# leer2.net
KiCad netlist of a schematic drawn in EAGLE
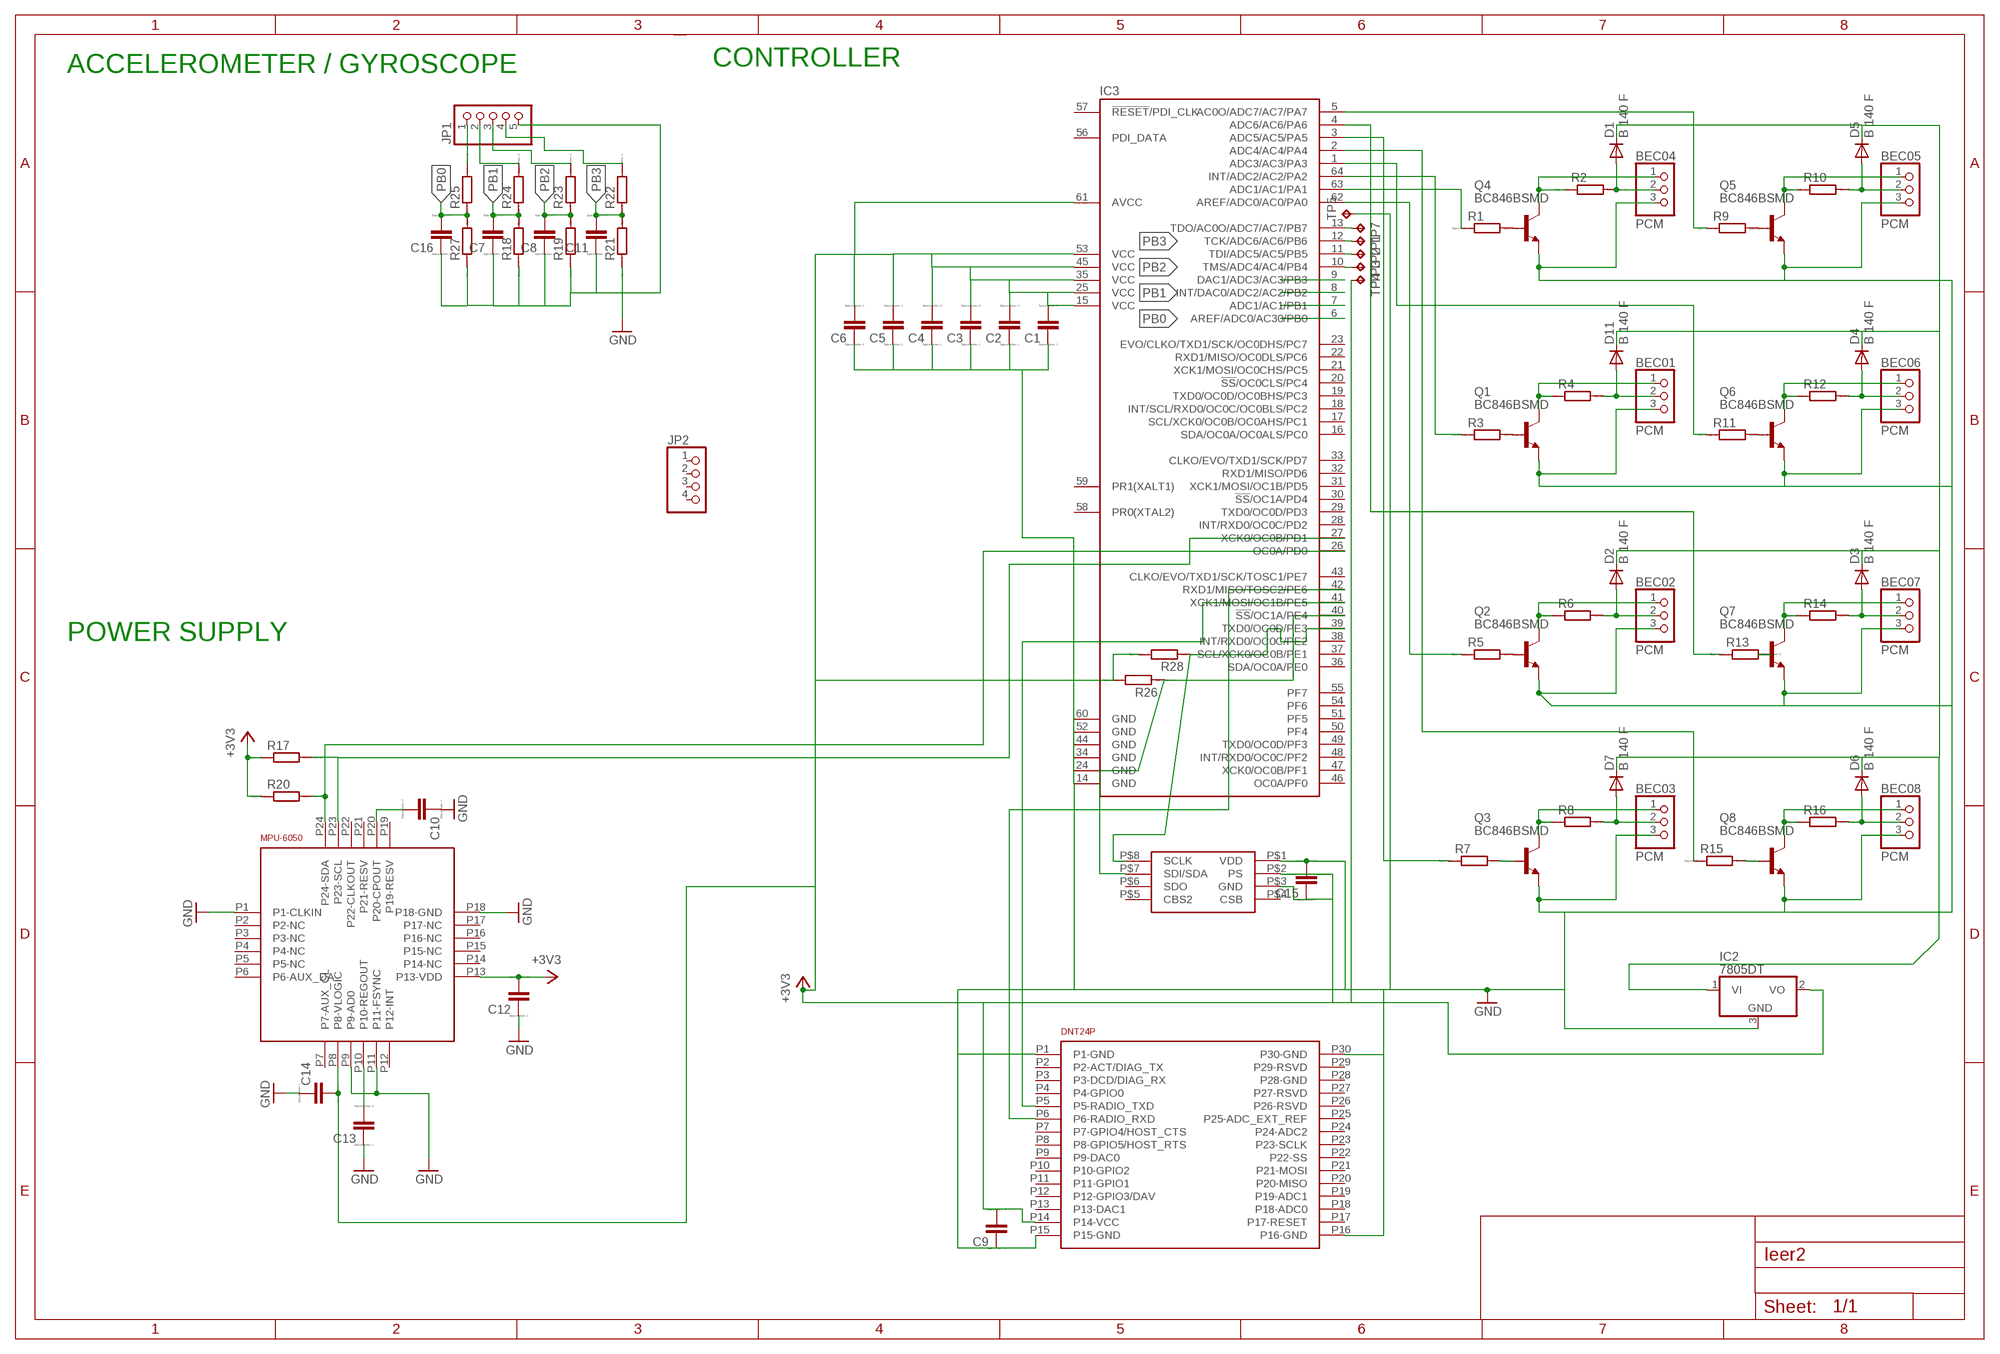
[diagram p0: schematic, sheet 1]

(export (version "E")
  (design (tool "Eeschema 10.0.6"))
  (components
    (comp (ref "BEC01")
      (value "PCM")
      (footprint "eagle-import:1X03")
      (libsource (lib "eagle-import") (part "PINHD-1X3"))
    )
    (comp (ref "BEC02")
      (value "PCM")
      (footprint "eagle-import:1X03")
      (libsource (lib "eagle-import") (part "PINHD-1X3"))
    )
    (comp (ref "BEC03")
      (value "PCM")
      (footprint "eagle-import:1X03")
      (libsource (lib "eagle-import") (part "PINHD-1X3"))
    )
    (comp (ref "BEC04")
      (value "PCM")
      (footprint "eagle-import:1X03")
      (libsource (lib "eagle-import") (part "PINHD-1X3"))
    )
    (comp (ref "BEC05")
      (value "PCM")
      (footprint "eagle-import:1X03")
      (libsource (lib "eagle-import") (part "PINHD-1X3"))
    )
    (comp (ref "BEC06")
      (value "PCM")
      (footprint "eagle-import:1X03")
      (libsource (lib "eagle-import") (part "PINHD-1X3"))
    )
    (comp (ref "BEC07")
      (value "PCM")
      (footprint "eagle-import:1X03")
      (libsource (lib "eagle-import") (part "PINHD-1X3"))
    )
    (comp (ref "BEC08")
      (value "PCM")
      (footprint "eagle-import:1X03")
      (libsource (lib "eagle-import") (part "PINHD-1X3"))
    )
    (comp (ref "C1")
      (value "CC0603")
      (footprint "eagle-import:C0603")
      (libsource (lib "eagle-import") (part "CC0603"))
    )
    (comp (ref "C2")
      (value "CC0603")
      (footprint "eagle-import:C0603")
      (libsource (lib "eagle-import") (part "CC0603"))
    )
    (comp (ref "C3")
      (value "CC0603")
      (footprint "eagle-import:C0603")
      (libsource (lib "eagle-import") (part "CC0603"))
    )
    (comp (ref "C4")
      (value "CC0603")
      (footprint "eagle-import:C0603")
      (libsource (lib "eagle-import") (part "CC0603"))
    )
    (comp (ref "C5")
      (value "CC0603")
      (footprint "eagle-import:C0603")
      (libsource (lib "eagle-import") (part "CC0603"))
    )
    (comp (ref "C6")
      (value "CC0603")
      (footprint "eagle-import:C0603")
      (libsource (lib "eagle-import") (part "CC0603"))
    )
    (comp (ref "C7")
      (value "CC0603")
      (footprint "eagle-import:C0603")
      (libsource (lib "eagle-import") (part "CC0603"))
    )
    (comp (ref "C8")
      (value "CC0603")
      (footprint "eagle-import:C0603")
      (libsource (lib "eagle-import") (part "CC0603"))
    )
    (comp (ref "C9")
      (value "CC0603")
      (footprint "eagle-import:C0603")
      (libsource (lib "eagle-import") (part "CC0603"))
    )
    (comp (ref "C10")
      (value "CC0603")
      (footprint "eagle-import:C0603")
      (libsource (lib "eagle-import") (part "CC0603"))
    )
    (comp (ref "C11")
      (value "CC0603")
      (footprint "eagle-import:C0603")
      (libsource (lib "eagle-import") (part "CC0603"))
    )
    (comp (ref "C12")
      (value "CC0603")
      (footprint "eagle-import:C0603")
      (libsource (lib "eagle-import") (part "CC0603"))
    )
    (comp (ref "C13")
      (value "CC0603")
      (footprint "eagle-import:C0603")
      (libsource (lib "eagle-import") (part "CC0603"))
    )
    (comp (ref "C14")
      (value "CC0603")
      (footprint "eagle-import:C0603")
      (libsource (lib "eagle-import") (part "CC0603"))
    )
    (comp (ref "C15")
      (value "CC0603")
      (footprint "eagle-import:C0603")
      (libsource (lib "eagle-import") (part "CC0603"))
    )
    (comp (ref "C16")
      (value "CC0603")
      (footprint "eagle-import:C0603")
      (libsource (lib "eagle-import") (part "CC0603"))
    )
    (comp (ref "D1")
      (value "B 140 F")
      (footprint "eagle-import:SOD-123_MINI-SMA")
      (libsource (lib "eagle-import") (part "CGRM400-G1"))
    )
    (comp (ref "D2")
      (value "B 140 F")
      (footprint "eagle-import:SOD-123_MINI-SMA")
      (libsource (lib "eagle-import") (part "CGRM400-G1"))
    )
    (comp (ref "D3")
      (value "B 140 F")
      (footprint "eagle-import:SOD-123_MINI-SMA")
      (libsource (lib "eagle-import") (part "CGRM400-G1"))
    )
    (comp (ref "D4")
      (value "B 140 F")
      (footprint "eagle-import:SOD-123_MINI-SMA")
      (libsource (lib "eagle-import") (part "CGRM400-G1"))
    )
    (comp (ref "D5")
      (value "B 140 F")
      (footprint "eagle-import:SOD-123_MINI-SMA")
      (libsource (lib "eagle-import") (part "CGRM400-G1"))
    )
    (comp (ref "D6")
      (value "B 140 F")
      (footprint "eagle-import:SOD-123_MINI-SMA")
      (libsource (lib "eagle-import") (part "CGRM400-G1"))
    )
    (comp (ref "D7")
      (value "B 140 F")
      (footprint "eagle-import:SOD-123_MINI-SMA")
      (libsource (lib "eagle-import") (part "CGRM400-G1"))
    )
    (comp (ref "D11")
      (value "B 140 F")
      (footprint "eagle-import:SOD-123_MINI-SMA")
      (libsource (lib "eagle-import") (part "CGRM400-G1"))
    )
    (comp (ref "IC2")
      (value "7805DT")
      (footprint "eagle-import:TO252")
      (libsource (lib "eagle-import") (part "78DT05"))
    )
    (comp (ref "IC3")
      (value "ATXMEGA##A3-64A")
      (footprint "eagle-import:TQFP-64")
      (libsource (lib "eagle-import") (part "ATXMEGA##A3-64A"))
    )
    (comp (ref "JP1")
      (value "PINHD-1X5/90")
      (footprint "eagle-import:1X05_90")
      (libsource (lib "eagle-import") (part "PINHD-1X5/90"))
    )
    (comp (ref "JP2")
      (value "PINHD-1X4/90")
      (footprint "eagle-import:1X04_90")
      (libsource (lib "eagle-import") (part "PINHD-1X4/90"))
    )
    (comp (ref "Q1")
      (value "BC846BSMD")
      (footprint "eagle-import:SOT23")
      (libsource (lib "eagle-import") (part "BC846SMDB"))
    )
    (comp (ref "Q2")
      (value "BC846BSMD")
      (footprint "eagle-import:SOT23")
      (libsource (lib "eagle-import") (part "BC846SMDB"))
    )
    (comp (ref "Q3")
      (value "BC846BSMD")
      (footprint "eagle-import:SOT23")
      (libsource (lib "eagle-import") (part "BC846SMDB"))
    )
    (comp (ref "Q4")
      (value "BC846BSMD")
      (footprint "eagle-import:SOT23")
      (libsource (lib "eagle-import") (part "BC846SMDB"))
    )
    (comp (ref "Q5")
      (value "BC846BSMD")
      (footprint "eagle-import:SOT23")
      (libsource (lib "eagle-import") (part "BC846SMDB"))
    )
    (comp (ref "Q6")
      (value "BC846BSMD")
      (footprint "eagle-import:SOT23")
      (libsource (lib "eagle-import") (part "BC846SMDB"))
    )
    (comp (ref "Q7")
      (value "BC846BSMD")
      (footprint "eagle-import:SOT23")
      (libsource (lib "eagle-import") (part "BC846SMDB"))
    )
    (comp (ref "Q8")
      (value "BC846BSMD")
      (footprint "eagle-import:SOT23")
      (libsource (lib "eagle-import") (part "BC846SMDB"))
    )
    (comp (ref "R1")
      (value "RR0603")
      (footprint "eagle-import:R0603")
      (libsource (lib "eagle-import") (part "RR0603"))
    )
    (comp (ref "R2")
      (value "RR0603")
      (footprint "eagle-import:R0603")
      (libsource (lib "eagle-import") (part "RR0603"))
    )
    (comp (ref "R3")
      (value "RR0603")
      (footprint "eagle-import:R0603")
      (libsource (lib "eagle-import") (part "RR0603"))
    )
    (comp (ref "R4")
      (value "RR0603")
      (footprint "eagle-import:R0603")
      (libsource (lib "eagle-import") (part "RR0603"))
    )
    (comp (ref "R5")
      (value "RR0603")
      (footprint "eagle-import:R0603")
      (libsource (lib "eagle-import") (part "RR0603"))
    )
    (comp (ref "R6")
      (value "RR0603")
      (footprint "eagle-import:R0603")
      (libsource (lib "eagle-import") (part "RR0603"))
    )
    (comp (ref "R7")
      (value "RR0603")
      (footprint "eagle-import:R0603")
      (libsource (lib "eagle-import") (part "RR0603"))
    )
    (comp (ref "R8")
      (value "RR0603")
      (footprint "eagle-import:R0603")
      (libsource (lib "eagle-import") (part "RR0603"))
    )
    (comp (ref "R9")
      (value "RR0603")
      (footprint "eagle-import:R0603")
      (libsource (lib "eagle-import") (part "RR0603"))
    )
    (comp (ref "R10")
      (value "RR0603")
      (footprint "eagle-import:R0603")
      (libsource (lib "eagle-import") (part "RR0603"))
    )
    (comp (ref "R11")
      (value "RR0603")
      (footprint "eagle-import:R0603")
      (libsource (lib "eagle-import") (part "RR0603"))
    )
    (comp (ref "R12")
      (value "RR0603")
      (footprint "eagle-import:R0603")
      (libsource (lib "eagle-import") (part "RR0603"))
    )
    (comp (ref "R13")
      (value "RR0603")
      (footprint "eagle-import:R0603")
      (libsource (lib "eagle-import") (part "RR0603"))
    )
    (comp (ref "R14")
      (value "RR0603")
      (footprint "eagle-import:R0603")
      (libsource (lib "eagle-import") (part "RR0603"))
    )
    (comp (ref "R15")
      (value "RR0603")
      (footprint "eagle-import:R0603")
      (libsource (lib "eagle-import") (part "RR0603"))
    )
    (comp (ref "R16")
      (value "RR0603")
      (footprint "eagle-import:R0603")
      (libsource (lib "eagle-import") (part "RR0603"))
    )
    (comp (ref "R17")
      (value "RR0603")
      (footprint "eagle-import:R0603")
      (libsource (lib "eagle-import") (part "RR0603"))
    )
    (comp (ref "R18")
      (value "RR0603")
      (footprint "eagle-import:R0603")
      (libsource (lib "eagle-import") (part "RR0603"))
    )
    (comp (ref "R19")
      (value "RR0603")
      (footprint "eagle-import:R0603")
      (libsource (lib "eagle-import") (part "RR0603"))
    )
    (comp (ref "R20")
      (value "RR0603")
      (footprint "eagle-import:R0603")
      (libsource (lib "eagle-import") (part "RR0603"))
    )
    (comp (ref "R21")
      (value "RR0603")
      (footprint "eagle-import:R0603")
      (libsource (lib "eagle-import") (part "RR0603"))
    )
    (comp (ref "R22")
      (value "RR0603")
      (footprint "eagle-import:R0603")
      (libsource (lib "eagle-import") (part "RR0603"))
    )
    (comp (ref "R23")
      (value "RR0603")
      (footprint "eagle-import:R0603")
      (libsource (lib "eagle-import") (part "RR0603"))
    )
    (comp (ref "R24")
      (value "RR0603")
      (footprint "eagle-import:R0603")
      (libsource (lib "eagle-import") (part "RR0603"))
    )
    (comp (ref "R25")
      (value "RR0603")
      (footprint "eagle-import:R0603")
      (libsource (lib "eagle-import") (part "RR0603"))
    )
    (comp (ref "R26")
      (value "RR0603")
      (footprint "eagle-import:R0603")
      (libsource (lib "eagle-import") (part "RR0603"))
    )
    (comp (ref "R27")
      (value "RR0603")
      (footprint "eagle-import:R0603")
      (libsource (lib "eagle-import") (part "RR0603"))
    )
    (comp (ref "R28")
      (value "RR0603")
      (footprint "eagle-import:R0603")
      (libsource (lib "eagle-import") (part "RR0603"))
    )
    (comp (ref "TP1")
      (value "TPTP08R")
      (footprint "eagle-import:TP08R")
      (libsource (lib "eagle-import") (part "TPTP08R"))
    )
    (comp (ref "TP2")
      (value "TPTP08R")
      (footprint "eagle-import:TP08R")
      (libsource (lib "eagle-import") (part "TPTP08R"))
    )
    (comp (ref "TP3")
      (value "TPTP08R")
      (footprint "eagle-import:TP08R")
      (libsource (lib "eagle-import") (part "TPTP08R"))
    )
    (comp (ref "TP4")
      (value "TPTP08R")
      (footprint "eagle-import:TP08R")
      (libsource (lib "eagle-import") (part "TPTP08R"))
    )
    (comp (ref "TP5")
      (value "TPTP08R")
      (footprint "eagle-import:TP08R")
      (libsource (lib "eagle-import") (part "TPTP08R"))
    )
    (comp (ref "TP7")
      (value "TPTP08R")
      (footprint "eagle-import:TP08R")
      (libsource (lib "eagle-import") (part "TPTP08R"))
    )
    (comp (ref "U$1")
      (value "DNT24P_RADIO_MODULE")
      (footprint "eagle-import:DNT24P_RADIO_MODULE")
      (libsource (lib "eagle-import") (part "DNT24P_RADIO_MODULE"))
    )
    (comp (ref "U$2")
      (value "MS5611")
      (footprint "eagle-import:01BA03")
      (libsource (lib "eagle-import") (part "MS5611"))
    )
    (comp (ref "U$3")
      (value "MPU-6050_ACC_GYRO")
      (footprint "eagle-import:MPU-6050_ACC_GYRO")
      (libsource (lib "eagle-import") (part "MPU-6050_ACC_GYRO"))
    )
  )
  (nets
    (net (code "1") (name "+3V3") (class "Default")
      (node (ref "C1") (pin "2") (pinfunction "2_2") (pintype "passive"))
      (node (ref "C12") (pin "2") (pinfunction "2_2") (pintype "passive"))
      (node (ref "C14") (pin "2") (pinfunction "2_2") (pintype "passive"))
      (node (ref "C15") (pin "1") (pinfunction "1_1") (pintype "passive"))
      (node (ref "C2") (pin "2") (pinfunction "2_2") (pintype "passive"))
      (node (ref "C3") (pin "2") (pinfunction "2_2") (pintype "passive"))
      (node (ref "C4") (pin "2") (pinfunction "2_2") (pintype "passive"))
      (node (ref "C5") (pin "2") (pinfunction "2_2") (pintype "passive"))
      (node (ref "C6") (pin "2") (pinfunction "2_2") (pintype "passive"))
      (node (ref "C9") (pin "2") (pinfunction "2_2") (pintype "passive"))
      (node (ref "IC2") (pin "2") (pinfunction "VO_2") (pintype "passive"))
      (node (ref "IC3") (pin "15") (pinfunction "VCC_15") (pintype "power_in"))
      (node (ref "IC3") (pin "25") (pinfunction "VCC_25") (pintype "power_in"))
      (node (ref "IC3") (pin "35") (pinfunction "VCC_35") (pintype "power_in"))
      (node (ref "IC3") (pin "45") (pinfunction "VCC_45") (pintype "power_in"))
      (node (ref "IC3") (pin "53") (pinfunction "VCC_53") (pintype "power_in"))
      (node (ref "IC3") (pin "61") (pinfunction "AVCC_61") (pintype "power_in"))
      (node (ref "R17") (pin "1") (pinfunction "1_1") (pintype "passive"))
      (node (ref "R20") (pin "1") (pinfunction "1_1") (pintype "passive"))
      (node (ref "R26") (pin "2") (pinfunction "2_2") (pintype "passive"))
      (node (ref "R28") (pin "2") (pinfunction "2_2") (pintype "passive"))
      (node (ref "TP4") (pin "TP") (pinfunction "TP_TP") (pintype "input"))
      (node (ref "U$1") (pin "P14") (pinfunction "P14-VCC_P14") (pintype "bidirectional"))
      (node (ref "U$2") (pin "P$2") (pinfunction "PS_P$2") (pintype "bidirectional"))
      (node (ref "U$2") (pin "P$3") (pinfunction "GND_P$3") (pintype "bidirectional"))
      (node (ref "U$3") (pin "P13") (pinfunction "P13-VDD_P13") (pintype "bidirectional"))
      (node (ref "U$3") (pin "P8") (pinfunction "P8-VLOGIC_P8") (pintype "bidirectional"))
    )
    (net (code "2") (name "GND") (class "Default")
      (node (ref "BEC01") (pin "3") (pinfunction "3_3") (pintype "passive"))
      (node (ref "BEC02") (pin "3") (pinfunction "3_3") (pintype "passive"))
      (node (ref "BEC03") (pin "3") (pinfunction "3_3") (pintype "passive"))
      (node (ref "BEC04") (pin "3") (pinfunction "3_3") (pintype "passive"))
      (node (ref "BEC05") (pin "3") (pinfunction "3_3") (pintype "passive"))
      (node (ref "BEC06") (pin "3") (pinfunction "3_3") (pintype "passive"))
      (node (ref "BEC07") (pin "3") (pinfunction "3_3") (pintype "passive"))
      (node (ref "BEC08") (pin "3") (pinfunction "3_3") (pintype "passive"))
      (node (ref "C1") (pin "1") (pinfunction "1_1") (pintype "passive"))
      (node (ref "C10") (pin "1") (pinfunction "1_1") (pintype "passive"))
      (node (ref "C11") (pin "1") (pinfunction "1_1") (pintype "passive"))
      (node (ref "C12") (pin "1") (pinfunction "1_1") (pintype "passive"))
      (node (ref "C13") (pin "1") (pinfunction "1_1") (pintype "passive"))
      (node (ref "C14") (pin "1") (pinfunction "1_1") (pintype "passive"))
      (node (ref "C15") (pin "2") (pinfunction "2_2") (pintype "passive"))
      (node (ref "C16") (pin "1") (pinfunction "1_1") (pintype "passive"))
      (node (ref "C2") (pin "1") (pinfunction "1_1") (pintype "passive"))
      (node (ref "C3") (pin "1") (pinfunction "1_1") (pintype "passive"))
      (node (ref "C4") (pin "1") (pinfunction "1_1") (pintype "passive"))
      (node (ref "C5") (pin "1") (pinfunction "1_1") (pintype "passive"))
      (node (ref "C6") (pin "1") (pinfunction "1_1") (pintype "passive"))
      (node (ref "C7") (pin "1") (pinfunction "1_1") (pintype "passive"))
      (node (ref "C8") (pin "1") (pinfunction "1_1") (pintype "passive"))
      (node (ref "C9") (pin "1") (pinfunction "1_1") (pintype "passive"))
      (node (ref "IC2") (pin "3") (pinfunction "GND_3") (pintype "passive"))
      (node (ref "IC3") (pin "14") (pinfunction "GND_14") (pintype "power_in"))
      (node (ref "IC3") (pin "24") (pinfunction "GND_24") (pintype "power_in"))
      (node (ref "IC3") (pin "34") (pinfunction "GND_34") (pintype "power_in"))
      (node (ref "IC3") (pin "44") (pinfunction "GND_44") (pintype "power_in"))
      (node (ref "IC3") (pin "52") (pinfunction "GND_52") (pintype "power_in"))
      (node (ref "IC3") (pin "60") (pinfunction "GND_60") (pintype "power_in"))
      (node (ref "JP1") (pin "5") (pinfunction "5_5") (pintype "passive"))
      (node (ref "Q1") (pin "2") (pinfunction "E_2") (pintype "passive"))
      (node (ref "Q2") (pin "2") (pinfunction "E_2") (pintype "passive"))
      (node (ref "Q3") (pin "2") (pinfunction "E_2") (pintype "passive"))
      (node (ref "Q4") (pin "2") (pinfunction "E_2") (pintype "passive"))
      (node (ref "Q5") (pin "2") (pinfunction "E_2") (pintype "passive"))
      (node (ref "Q6") (pin "2") (pinfunction "E_2") (pintype "passive"))
      (node (ref "Q7") (pin "2") (pinfunction "E_2") (pintype "passive"))
      (node (ref "Q8") (pin "2") (pinfunction "E_2") (pintype "passive"))
      (node (ref "R18") (pin "1") (pinfunction "1_1") (pintype "passive"))
      (node (ref "R19") (pin "1") (pinfunction "1_1") (pintype "passive"))
      (node (ref "R21") (pin "1") (pinfunction "1_1") (pintype "passive"))
      (node (ref "R27") (pin "1") (pinfunction "1_1") (pintype "passive"))
      (node (ref "TP5") (pin "TP") (pinfunction "TP_TP") (pintype "input"))
      (node (ref "U$1") (pin "P1") (pinfunction "P1-GND_P1") (pintype "bidirectional"))
      (node (ref "U$1") (pin "P15") (pinfunction "P15-GND_P15") (pintype "bidirectional"))
      (node (ref "U$1") (pin "P16") (pinfunction "P16-GND_P16") (pintype "bidirectional"))
      (node (ref "U$1") (pin "P30") (pinfunction "P30-GND_P30") (pintype "bidirectional"))
      (node (ref "U$2") (pin "P$1") (pinfunction "VDD_P$1") (pintype "bidirectional"))
      (node (ref "U$3") (pin "P1") (pinfunction "P1-CLKIN_P1") (pintype "bidirectional"))
      (node (ref "U$3") (pin "P11") (pinfunction "P11-FSYNC_P11") (pintype "bidirectional"))
      (node (ref "U$3") (pin "P18") (pinfunction "P18-GND_P18") (pintype "bidirectional"))
      (node (ref "U$3") (pin "P9") (pinfunction "P9-AD0_P9") (pintype "bidirectional"))
    )
    (net (code "3") (name "Net-(BEC01-Pad2)") (class "Default")
      (node (ref "BEC01") (pin "2") (pinfunction "2_2") (pintype "passive"))
      (node (ref "D11") (pin "A") (pinfunction "A_A") (pintype "passive"))
      (node (ref "R4") (pin "2") (pinfunction "2_2") (pintype "passive"))
    )
    (net (code "4") (name "Net-(BEC02-Pad2)") (class "Default")
      (node (ref "BEC02") (pin "2") (pinfunction "2_2") (pintype "passive"))
      (node (ref "D2") (pin "A") (pinfunction "A_A") (pintype "passive"))
      (node (ref "R6") (pin "2") (pinfunction "2_2") (pintype "passive"))
    )
    (net (code "5") (name "Net-(BEC03-Pad2)") (class "Default")
      (node (ref "BEC03") (pin "2") (pinfunction "2_2") (pintype "passive"))
      (node (ref "D7") (pin "A") (pinfunction "A_A") (pintype "passive"))
      (node (ref "R8") (pin "2") (pinfunction "2_2") (pintype "passive"))
    )
    (net (code "6") (name "Net-(BEC04-Pad2)") (class "Default")
      (node (ref "BEC04") (pin "2") (pinfunction "2_2") (pintype "passive"))
      (node (ref "D1") (pin "A") (pinfunction "A_A") (pintype "passive"))
      (node (ref "R2") (pin "2") (pinfunction "2_2") (pintype "passive"))
    )
    (net (code "7") (name "Net-(BEC05-Pad2)") (class "Default")
      (node (ref "BEC05") (pin "2") (pinfunction "2_2") (pintype "passive"))
      (node (ref "D5") (pin "A") (pinfunction "A_A") (pintype "passive"))
      (node (ref "R10") (pin "2") (pinfunction "2_2") (pintype "passive"))
    )
    (net (code "8") (name "Net-(BEC06-Pad2)") (class "Default")
      (node (ref "BEC06") (pin "2") (pinfunction "2_2") (pintype "passive"))
      (node (ref "D4") (pin "A") (pinfunction "A_A") (pintype "passive"))
      (node (ref "R12") (pin "2") (pinfunction "2_2") (pintype "passive"))
    )
    (net (code "9") (name "Net-(BEC07-Pad2)") (class "Default")
      (node (ref "BEC07") (pin "2") (pinfunction "2_2") (pintype "passive"))
      (node (ref "D3") (pin "A") (pinfunction "A_A") (pintype "passive"))
      (node (ref "R14") (pin "2") (pinfunction "2_2") (pintype "passive"))
    )
    (net (code "10") (name "Net-(BEC08-Pad2)") (class "Default")
      (node (ref "BEC08") (pin "2") (pinfunction "2_2") (pintype "passive"))
      (node (ref "D6") (pin "A") (pinfunction "A_A") (pintype "passive"))
      (node (ref "R16") (pin "2") (pinfunction "2_2") (pintype "passive"))
    )
    (net (code "11") (name "Net-(IC2-VI)") (class "Default")
      (node (ref "D1") (pin "C") (pinfunction "C_C") (pintype "passive"))
      (node (ref "D11") (pin "C") (pinfunction "C_C") (pintype "passive"))
      (node (ref "D2") (pin "C") (pinfunction "C_C") (pintype "passive"))
      (node (ref "D3") (pin "C") (pinfunction "C_C") (pintype "passive"))
      (node (ref "D4") (pin "C") (pinfunction "C_C") (pintype "passive"))
      (node (ref "D5") (pin "C") (pinfunction "C_C") (pintype "passive"))
      (node (ref "D6") (pin "C") (pinfunction "C_C") (pintype "passive"))
      (node (ref "D7") (pin "C") (pinfunction "C_C") (pintype "passive"))
      (node (ref "IC2") (pin "1") (pinfunction "VI_1") (pintype "input"))
    )
    (net (code "12") (name "Net-(IC3-AC0O{slash}ADC7{slash}AC7{slash}PA7)") (class "Default")
      (node (ref "IC3") (pin "5") (pinfunction "AC0O/ADC7/AC7/PA7_5") (pintype "bidirectional"))
      (node (ref "R9") (pin "1") (pinfunction "1_1") (pintype "passive"))
    )
    (net (code "13") (name "Net-(IC3-ADC1{slash}AC1{slash}PA1)") (class "Default")
      (node (ref "IC3") (pin "63") (pinfunction "ADC1/AC1/PA1_63") (pintype "bidirectional"))
      (node (ref "R1") (pin "1") (pinfunction "1_1") (pintype "passive"))
    )
    (net (code "14") (name "Net-(IC3-ADC3{slash}AC3{slash}PA3)") (class "Default")
      (node (ref "IC3") (pin "1") (pinfunction "ADC3/AC3/PA3_1") (pintype "bidirectional"))
      (node (ref "R11") (pin "1") (pinfunction "1_1") (pintype "passive"))
    )
    (net (code "15") (name "Net-(IC3-ADC4{slash}AC4{slash}PA4)") (class "Default")
      (node (ref "IC3") (pin "2") (pinfunction "ADC4/AC4/PA4_2") (pintype "bidirectional"))
      (node (ref "R15") (pin "1") (pinfunction "1_1") (pintype "passive"))
    )
    (net (code "16") (name "Net-(IC3-ADC5{slash}AC5{slash}PA5)") (class "Default")
      (node (ref "IC3") (pin "3") (pinfunction "ADC5/AC5/PA5_3") (pintype "bidirectional"))
      (node (ref "R7") (pin "1") (pinfunction "1_1") (pintype "passive"))
    )
    (net (code "17") (name "Net-(IC3-ADC6{slash}AC6{slash}PA6)") (class "Default")
      (node (ref "IC3") (pin "4") (pinfunction "ADC6/AC6/PA6_4") (pintype "bidirectional"))
      (node (ref "R13") (pin "1") (pinfunction "1_1") (pintype "passive"))
    )
    (net (code "18") (name "Net-(IC3-AREF{slash}ADC0{slash}AC0{slash}PA0)") (class "Default")
      (node (ref "IC3") (pin "62") (pinfunction "AREF/ADC0/AC0/PA0_62") (pintype "bidirectional"))
      (node (ref "R5") (pin "1") (pinfunction "1_1") (pintype "passive"))
    )
    (net (code "19") (name "Net-(IC3-INT{slash}ADC2{slash}AC2{slash}PA2)") (class "Default")
      (node (ref "IC3") (pin "64") (pinfunction "INT/ADC2/AC2/PA2_64") (pintype "bidirectional"))
      (node (ref "R3") (pin "1") (pinfunction "1_1") (pintype "passive"))
    )
    (net (code "20") (name "Net-(IC3-OC0A{slash}PD0)") (class "Default")
      (node (ref "IC3") (pin "26") (pinfunction "OC0A/PD0_26") (pintype "bidirectional"))
      (node (ref "R20") (pin "2") (pinfunction "2_2") (pintype "passive"))
      (node (ref "U$3") (pin "P24") (pinfunction "P24-SDA_P24") (pintype "bidirectional"))
    )
    (net (code "21") (name "Net-(IC3-RXD1{slash}MISO{slash}TOSC2{slash}PE6)") (class "Default")
      (node (ref "IC3") (pin "42") (pinfunction "RXD1/MISO/TOSC2/PE6_42") (pintype "bidirectional"))
      (node (ref "U$1") (pin "P6") (pinfunction "P6-RADIO_RXD_P6") (pintype "bidirectional"))
    )
    (net (code "22") (name "Net-(IC3-TCK{slash}ADC6{slash}AC6{slash}PB6)") (class "Default")
      (node (ref "IC3") (pin "12") (pinfunction "TCK/ADC6/AC6/PB6_12") (pintype "bidirectional"))
      (node (ref "TP1") (pin "TP") (pinfunction "TP_TP") (pintype "input"))
    )
    (net (code "23") (name "Net-(IC3-TDI{slash}ADC5{slash}AC5{slash}PB5)") (class "Default")
      (node (ref "IC3") (pin "11") (pinfunction "TDI/ADC5/AC5/PB5_11") (pintype "bidirectional"))
      (node (ref "TP2") (pin "TP") (pinfunction "TP_TP") (pintype "input"))
    )
    (net (code "24") (name "Net-(IC3-TDO{slash}AC0O{slash}ADC7{slash}AC7{slash}PB7)") (class "Default")
      (node (ref "IC3") (pin "13") (pinfunction "TDO/AC0O/ADC7/AC7/PB7_13") (pintype "bidirectional"))
      (node (ref "TP7") (pin "TP") (pinfunction "TP_TP") (pintype "input"))
    )
    (net (code "25") (name "Net-(IC3-TMS{slash}ADC4{slash}AC4{slash}PB4)") (class "Default")
      (node (ref "IC3") (pin "10") (pinfunction "TMS/ADC4/AC4/PB4_10") (pintype "bidirectional"))
      (node (ref "TP3") (pin "TP") (pinfunction "TP_TP") (pintype "input"))
    )
    (net (code "26") (name "Net-(IC3-TXD0{slash}OC0D{slash}PE3)") (class "Default")
      (node (ref "IC3") (pin "39") (pinfunction "TXD0/OC0D/PE3_39") (pintype "bidirectional"))
      (node (ref "R28") (pin "1") (pinfunction "1_1") (pintype "passive"))
      (node (ref "U$2") (pin "P$8") (pinfunction "SCLK_P$8") (pintype "bidirectional"))
    )
    (net (code "27") (name "Net-(IC3-XCK0{slash}OC0B{slash}PD1)") (class "Default")
      (node (ref "IC3") (pin "27") (pinfunction "XCK0/OC0B/PD1_27") (pintype "bidirectional"))
      (node (ref "R17") (pin "2") (pinfunction "2_2") (pintype "passive"))
      (node (ref "U$3") (pin "P23") (pinfunction "P23-SCL_P23") (pintype "bidirectional"))
    )
    (net (code "28") (name "Net-(IC3-XCK1{slash}MOSI{slash}OC1B{slash}PE5)") (class "Default")
      (node (ref "IC3") (pin "41") (pinfunction "XCK1/MOSI/OC1B/PE5_41") (pintype "bidirectional"))
      (node (ref "U$1") (pin "P5") (pinfunction "P5-RADIO_TXD_P5") (pintype "bidirectional"))
    )
    (net (code "29") (name "Net-(IC3-~{SS}{slash}OC1A{slash}PE4)") (class "Default")
      (node (ref "IC3") (pin "40") (pinfunction "~{SS}/OC1A/PE4_40") (pintype "bidirectional"))
      (node (ref "R26") (pin "1") (pinfunction "1_1") (pintype "passive"))
      (node (ref "U$2") (pin "P$7") (pinfunction "SDI/SDA_P$7") (pintype "bidirectional"))
    )
    (net (code "30") (name "Net-(JP1-Pad1)") (class "Default")
      (node (ref "JP1") (pin "1") (pinfunction "1_1") (pintype "passive"))
      (node (ref "R25") (pin "2") (pinfunction "2_2") (pintype "passive"))
    )
    (net (code "31") (name "Net-(JP1-Pad2)") (class "Default")
      (node (ref "JP1") (pin "2") (pinfunction "2_2") (pintype "passive"))
      (node (ref "R24") (pin "2") (pinfunction "2_2") (pintype "passive"))
    )
    (net (code "32") (name "Net-(JP1-Pad3)") (class "Default")
      (node (ref "JP1") (pin "3") (pinfunction "3_3") (pintype "passive"))
      (node (ref "R23") (pin "2") (pinfunction "2_2") (pintype "passive"))
    )
    (net (code "33") (name "Net-(JP1-Pad4)") (class "Default")
      (node (ref "JP1") (pin "4") (pinfunction "4_4") (pintype "passive"))
      (node (ref "R22") (pin "2") (pinfunction "2_2") (pintype "passive"))
    )
    (net (code "34") (name "Net-(Q1-B)") (class "Default")
      (node (ref "Q1") (pin "1") (pinfunction "B_1") (pintype "passive"))
      (node (ref "R3") (pin "2") (pinfunction "2_2") (pintype "passive"))
    )
    (net (code "35") (name "Net-(Q1-C)") (class "Default")
      (node (ref "BEC01") (pin "1") (pinfunction "1_1") (pintype "passive"))
      (node (ref "Q1") (pin "3") (pinfunction "C_3") (pintype "passive"))
      (node (ref "R4") (pin "1") (pinfunction "1_1") (pintype "passive"))
    )
    (net (code "36") (name "Net-(Q2-B)") (class "Default")
      (node (ref "Q2") (pin "1") (pinfunction "B_1") (pintype "passive"))
      (node (ref "R5") (pin "2") (pinfunction "2_2") (pintype "passive"))
    )
    (net (code "37") (name "Net-(Q2-C)") (class "Default")
      (node (ref "BEC02") (pin "1") (pinfunction "1_1") (pintype "passive"))
      (node (ref "Q2") (pin "3") (pinfunction "C_3") (pintype "passive"))
      (node (ref "R6") (pin "1") (pinfunction "1_1") (pintype "passive"))
    )
    (net (code "38") (name "Net-(Q3-B)") (class "Default")
      (node (ref "Q3") (pin "1") (pinfunction "B_1") (pintype "passive"))
      (node (ref "R7") (pin "2") (pinfunction "2_2") (pintype "passive"))
    )
    (net (code "39") (name "Net-(Q3-C)") (class "Default")
      (node (ref "BEC03") (pin "1") (pinfunction "1_1") (pintype "passive"))
      (node (ref "Q3") (pin "3") (pinfunction "C_3") (pintype "passive"))
      (node (ref "R8") (pin "1") (pinfunction "1_1") (pintype "passive"))
    )
    (net (code "40") (name "Net-(Q4-B)") (class "Default")
      (node (ref "Q4") (pin "1") (pinfunction "B_1") (pintype "passive"))
      (node (ref "R1") (pin "2") (pinfunction "2_2") (pintype "passive"))
    )
    (net (code "41") (name "Net-(Q4-C)") (class "Default")
      (node (ref "BEC04") (pin "1") (pinfunction "1_1") (pintype "passive"))
      (node (ref "Q4") (pin "3") (pinfunction "C_3") (pintype "passive"))
      (node (ref "R2") (pin "1") (pinfunction "1_1") (pintype "passive"))
    )
    (net (code "42") (name "Net-(Q5-B)") (class "Default")
      (node (ref "Q5") (pin "1") (pinfunction "B_1") (pintype "passive"))
      (node (ref "R9") (pin "2") (pinfunction "2_2") (pintype "passive"))
    )
    (net (code "43") (name "Net-(Q5-C)") (class "Default")
      (node (ref "BEC05") (pin "1") (pinfunction "1_1") (pintype "passive"))
      (node (ref "Q5") (pin "3") (pinfunction "C_3") (pintype "passive"))
      (node (ref "R10") (pin "1") (pinfunction "1_1") (pintype "passive"))
    )
    (net (code "44") (name "Net-(Q6-B)") (class "Default")
      (node (ref "Q6") (pin "1") (pinfunction "B_1") (pintype "passive"))
      (node (ref "R11") (pin "2") (pinfunction "2_2") (pintype "passive"))
    )
    (net (code "45") (name "Net-(Q6-C)") (class "Default")
      (node (ref "BEC06") (pin "1") (pinfunction "1_1") (pintype "passive"))
      (node (ref "Q6") (pin "3") (pinfunction "C_3") (pintype "passive"))
      (node (ref "R12") (pin "1") (pinfunction "1_1") (pintype "passive"))
    )
    (net (code "46") (name "Net-(Q7-B)") (class "Default")
      (node (ref "Q7") (pin "1") (pinfunction "B_1") (pintype "passive"))
      (node (ref "R13") (pin "2") (pinfunction "2_2") (pintype "passive"))
    )
    (net (code "47") (name "Net-(Q7-C)") (class "Default")
      (node (ref "BEC07") (pin "1") (pinfunction "1_1") (pintype "passive"))
      (node (ref "Q7") (pin "3") (pinfunction "C_3") (pintype "passive"))
      (node (ref "R14") (pin "1") (pinfunction "1_1") (pintype "passive"))
    )
    (net (code "48") (name "Net-(Q8-B)") (class "Default")
      (node (ref "Q8") (pin "1") (pinfunction "B_1") (pintype "passive"))
      (node (ref "R15") (pin "2") (pinfunction "2_2") (pintype "passive"))
    )
    (net (code "49") (name "Net-(Q8-C)") (class "Default")
      (node (ref "BEC08") (pin "1") (pinfunction "1_1") (pintype "passive"))
      (node (ref "Q8") (pin "3") (pinfunction "C_3") (pintype "passive"))
      (node (ref "R16") (pin "1") (pinfunction "1_1") (pintype "passive"))
    )
    (net (code "50") (name "Net-(U$3-P10-REGOUT)") (class "Default")
      (node (ref "C13") (pin "2") (pinfunction "2_2") (pintype "passive"))
      (node (ref "U$3") (pin "P10") (pinfunction "P10-REGOUT_P10") (pintype "bidirectional"))
    )
    (net (code "51") (name "Net-(U$3-P20-CPOUT)") (class "Default")
      (node (ref "C10") (pin "2") (pinfunction "2_2") (pintype "passive"))
      (node (ref "U$3") (pin "P20") (pinfunction "P20-CPOUT_P20") (pintype "bidirectional"))
    )
    (net (code "52") (name "PB0") (class "Default")
      (node (ref "C16") (pin "2") (pinfunction "2_2") (pintype "passive"))
      (node (ref "IC3") (pin "6") (pinfunction "AREF/ADC0/AC30/PB0_6") (pintype "bidirectional"))
      (node (ref "R25") (pin "1") (pinfunction "1_1") (pintype "passive"))
      (node (ref "R27") (pin "2") (pinfunction "2_2") (pintype "passive"))
    )
    (net (code "53") (name "PB1") (class "Default")
      (node (ref "C7") (pin "2") (pinfunction "2_2") (pintype "passive"))
      (node (ref "IC3") (pin "7") (pinfunction "ADC1/AC1/PB1_7") (pintype "bidirectional"))
      (node (ref "R18") (pin "2") (pinfunction "2_2") (pintype "passive"))
      (node (ref "R24") (pin "1") (pinfunction "1_1") (pintype "passive"))
    )
    (net (code "54") (name "PB2") (class "Default")
      (node (ref "C8") (pin "2") (pinfunction "2_2") (pintype "passive"))
      (node (ref "IC3") (pin "8") (pinfunction "INT/DAC0/ADC2/AC2/PB2_8") (pintype "bidirectional"))
      (node (ref "R19") (pin "2") (pinfunction "2_2") (pintype "passive"))
      (node (ref "R23") (pin "1") (pinfunction "1_1") (pintype "passive"))
    )
    (net (code "55") (name "PB3") (class "Default")
      (node (ref "C11") (pin "2") (pinfunction "2_2") (pintype "passive"))
      (node (ref "IC3") (pin "9") (pinfunction "DAC1/ADC3/AC3/PB3_9") (pintype "bidirectional"))
      (node (ref "R21") (pin "2") (pinfunction "2_2") (pintype "passive"))
      (node (ref "R22") (pin "1") (pinfunction "1_1") (pintype "passive"))
    )
    (net (code "56") (name "unconnected-(IC3-CLKO{slash}EVO{slash}TXD1{slash}SCK{slash}PD7-Pad33)") (class "Default")
      (node (ref "IC3") (pin "33") (pinfunction "CLKO/EVO/TXD1/SCK/PD7_33") (pintype "bidirectional"))
    )
    (net (code "57") (name "unconnected-(IC3-CLKO{slash}EVO{slash}TXD1{slash}SCK{slash}TOSC1{slash}PE7-Pad43)") (class "Default")
      (node (ref "IC3") (pin "43") (pinfunction "CLKO/EVO/TXD1/SCK/TOSC1/PE7_43") (pintype "bidirectional"))
    )
    (net (code "58") (name "unconnected-(IC3-EVO{slash}CLKO{slash}TXD1{slash}SCK{slash}OC0DHS{slash}PC7-Pad23)") (class "Default")
      (node (ref "IC3") (pin "23") (pinfunction "EVO/CLKO/TXD1/SCK/OC0DHS/PC7_23") (pintype "bidirectional"))
    )
    (net (code "59") (name "unconnected-(IC3-INT{slash}RXD0{slash}OC0C{slash}PD2-Pad28)") (class "Default")
      (node (ref "IC3") (pin "28") (pinfunction "INT/RXD0/OC0C/PD2_28") (pintype "bidirectional"))
    )
    (net (code "60") (name "unconnected-(IC3-INT{slash}RXD0{slash}OC0C{slash}PE2-Pad38)") (class "Default")
      (node (ref "IC3") (pin "38") (pinfunction "INT/RXD0/OC0C/PE2_38") (pintype "bidirectional"))
    )
    (net (code "61") (name "unconnected-(IC3-INT{slash}RXD0{slash}OC0C{slash}PF2-Pad48)") (class "Default")
      (node (ref "IC3") (pin "48") (pinfunction "INT/RXD0/OC0C/PF2_48") (pintype "bidirectional"))
    )
    (net (code "62") (name "unconnected-(IC3-INT{slash}SCL{slash}RXD0{slash}OC0C{slash}OC0BLS{slash}PC2-Pad18)") (class "Default")
      (node (ref "IC3") (pin "18") (pinfunction "INT/SCL/RXD0/OC0C/OC0BLS/PC2_18") (pintype "bidirectional"))
    )
    (net (code "63") (name "unconnected-(IC3-OC0A{slash}PF0-Pad46)") (class "Default")
      (node (ref "IC3") (pin "46") (pinfunction "OC0A/PF0_46") (pintype "bidirectional"))
    )
    (net (code "64") (name "unconnected-(IC3-PDI_DATA-Pad56)") (class "Default")
      (node (ref "IC3") (pin "56") (pinfunction "PDI_DATA_56") (pintype "bidirectional"))
    )
    (net (code "65") (name "unconnected-(IC3-PF4-Pad50)") (class "Default")
      (node (ref "IC3") (pin "50") (pinfunction "PF4_50") (pintype "bidirectional"))
    )
    (net (code "66") (name "unconnected-(IC3-PF5-Pad51)") (class "Default")
      (node (ref "IC3") (pin "51") (pinfunction "PF5_51") (pintype "bidirectional"))
    )
    (net (code "67") (name "unconnected-(IC3-PF6-Pad54)") (class "Default")
      (node (ref "IC3") (pin "54") (pinfunction "PF6_54") (pintype "bidirectional"))
    )
    (net (code "68") (name "unconnected-(IC3-PF7-Pad55)") (class "Default")
      (node (ref "IC3") (pin "55") (pinfunction "PF7_55") (pintype "bidirectional"))
    )
    (net (code "69") (name "unconnected-(IC3-PR0(XTAL2)-Pad58)") (class "Default")
      (node (ref "IC3") (pin "58") (pinfunction "PR0(XTAL2)_58") (pintype "passive"))
    )
    (net (code "70") (name "unconnected-(IC3-PR1(XALT1)-Pad59)") (class "Default")
      (node (ref "IC3") (pin "59") (pinfunction "PR1(XALT1)_59") (pintype "passive"))
    )
    (net (code "71") (name "unconnected-(IC3-RXD1{slash}MISO{slash}OC0DLS{slash}PC6-Pad22)") (class "Default")
      (node (ref "IC3") (pin "22") (pinfunction "RXD1/MISO/OC0DLS/PC6_22") (pintype "bidirectional"))
    )
    (net (code "72") (name "unconnected-(IC3-RXD1{slash}MISO{slash}PD6-Pad32)") (class "Default")
      (node (ref "IC3") (pin "32") (pinfunction "RXD1/MISO/PD6_32") (pintype "bidirectional"))
    )
    (net (code "73") (name "unconnected-(IC3-SCL{slash}XCK0{slash}OC0B{slash}OC0AHS{slash}PC1-Pad17)") (class "Default")
      (node (ref "IC3") (pin "17") (pinfunction "SCL/XCK0/OC0B/OC0AHS/PC1_17") (pintype "bidirectional"))
    )
    (net (code "74") (name "unconnected-(IC3-SCL{slash}XCK0{slash}OC0B{slash}PE1-Pad37)") (class "Default")
      (node (ref "IC3") (pin "37") (pinfunction "SCL/XCK0/OC0B/PE1_37") (pintype "bidirectional"))
    )
    (net (code "75") (name "unconnected-(IC3-SDA{slash}OC0A{slash}OC0ALS{slash}PC0-Pad16)") (class "Default")
      (node (ref "IC3") (pin "16") (pinfunction "SDA/OC0A/OC0ALS/PC0_16") (pintype "bidirectional"))
    )
    (net (code "76") (name "unconnected-(IC3-SDA{slash}OC0A{slash}PE0-Pad36)") (class "Default")
      (node (ref "IC3") (pin "36") (pinfunction "SDA/OC0A/PE0_36") (pintype "bidirectional"))
    )
    (net (code "77") (name "unconnected-(IC3-TXD0{slash}OC0D{slash}OC0BHS{slash}PC3-Pad19)") (class "Default")
      (node (ref "IC3") (pin "19") (pinfunction "TXD0/OC0D/OC0BHS/PC3_19") (pintype "bidirectional"))
    )
    (net (code "78") (name "unconnected-(IC3-TXD0{slash}OC0D{slash}PD3-Pad29)") (class "Default")
      (node (ref "IC3") (pin "29") (pinfunction "TXD0/OC0D/PD3_29") (pintype "bidirectional"))
    )
    (net (code "79") (name "unconnected-(IC3-TXD0{slash}OC0D{slash}PF3-Pad49)") (class "Default")
      (node (ref "IC3") (pin "49") (pinfunction "TXD0/OC0D/PF3_49") (pintype "bidirectional"))
    )
    (net (code "80") (name "unconnected-(IC3-XCK0{slash}OC0B{slash}PF1-Pad47)") (class "Default")
      (node (ref "IC3") (pin "47") (pinfunction "XCK0/OC0B/PF1_47") (pintype "bidirectional"))
    )
    (net (code "81") (name "unconnected-(IC3-XCK1{slash}MOSI{slash}OC0CHS{slash}PC5-Pad21)") (class "Default")
      (node (ref "IC3") (pin "21") (pinfunction "XCK1/MOSI/OC0CHS/PC5_21") (pintype "bidirectional"))
    )
    (net (code "82") (name "unconnected-(IC3-XCK1{slash}MOSI{slash}OC1B{slash}PD5-Pad31)") (class "Default")
      (node (ref "IC3") (pin "31") (pinfunction "XCK1/MOSI/OC1B/PD5_31") (pintype "bidirectional"))
    )
    (net (code "83") (name "unconnected-(IC3-~{RESET}{slash}PDI_CLK-Pad57)") (class "Default")
      (node (ref "IC3") (pin "57") (pinfunction "~{RESET}/PDI_CLK_57") (pintype "input"))
    )
    (net (code "84") (name "unconnected-(IC3-~{SS}{slash}OC0CLS{slash}PC4-Pad20)") (class "Default")
      (node (ref "IC3") (pin "20") (pinfunction "~{SS}/OC0CLS/PC4_20") (pintype "bidirectional"))
    )
    (net (code "85") (name "unconnected-(IC3-~{SS}{slash}OC1A{slash}PD4-Pad30)") (class "Default")
      (node (ref "IC3") (pin "30") (pinfunction "~{SS}/OC1A/PD4_30") (pintype "bidirectional"))
    )
    (net (code "86") (name "unconnected-(JP2-Pad1)") (class "Default")
      (node (ref "JP2") (pin "1") (pinfunction "1_1") (pintype "passive"))
    )
    (net (code "87") (name "unconnected-(JP2-Pad2)") (class "Default")
      (node (ref "JP2") (pin "2") (pinfunction "2_2") (pintype "passive"))
    )
    (net (code "88") (name "unconnected-(JP2-Pad3)") (class "Default")
      (node (ref "JP2") (pin "3") (pinfunction "3_3") (pintype "passive"))
    )
    (net (code "89") (name "unconnected-(JP2-Pad4)") (class "Default")
      (node (ref "JP2") (pin "4") (pinfunction "4_4") (pintype "passive"))
    )
    (net (code "90") (name "unconnected-(U$1-P2-ACT{slash}DIAG_TX-PadP2)") (class "Default")
      (node (ref "U$1") (pin "P2") (pinfunction "P2-ACT/DIAG_TX_P2") (pintype "bidirectional"))
    )
    (net (code "91") (name "unconnected-(U$1-P3-DCD{slash}DIAG_RX-PadP3)") (class "Default")
      (node (ref "U$1") (pin "P3") (pinfunction "P3-DCD/DIAG_RX_P3") (pintype "bidirectional"))
    )
    (net (code "92") (name "unconnected-(U$1-P4-GPIO0-PadP4)") (class "Default")
      (node (ref "U$1") (pin "P4") (pinfunction "P4-GPIO0_P4") (pintype "bidirectional"))
    )
    (net (code "93") (name "unconnected-(U$1-P7-GPIO4{slash}HOST_CTS-PadP7)") (class "Default")
      (node (ref "U$1") (pin "P7") (pinfunction "P7-GPIO4/HOST_CTS_P7") (pintype "bidirectional"))
    )
    (net (code "94") (name "unconnected-(U$1-P8-GPIO5{slash}HOST_RTS-PadP8)") (class "Default")
      (node (ref "U$1") (pin "P8") (pinfunction "P8-GPIO5/HOST_RTS_P8") (pintype "bidirectional"))
    )
    (net (code "95") (name "unconnected-(U$1-P9-DAC0-PadP9)") (class "Default")
      (node (ref "U$1") (pin "P9") (pinfunction "P9-DAC0_P9") (pintype "bidirectional"))
    )
    (net (code "96") (name "unconnected-(U$1-P10-GPIO2-PadP10)") (class "Default")
      (node (ref "U$1") (pin "P10") (pinfunction "P10-GPIO2_P10") (pintype "bidirectional"))
    )
    (net (code "97") (name "unconnected-(U$1-P11-GPIO1-PadP11)") (class "Default")
      (node (ref "U$1") (pin "P11") (pinfunction "P11-GPIO1_P11") (pintype "bidirectional"))
    )
    (net (code "98") (name "unconnected-(U$1-P12-GPIO3{slash}DAV-PadP12)") (class "Default")
      (node (ref "U$1") (pin "P12") (pinfunction "P12-GPIO3/DAV_P12") (pintype "bidirectional"))
    )
    (net (code "99") (name "unconnected-(U$1-P13-DAC1-PadP13)") (class "Default")
      (node (ref "U$1") (pin "P13") (pinfunction "P13-DAC1_P13") (pintype "bidirectional"))
    )
    (net (code "100") (name "unconnected-(U$1-P17-RESET-PadP17)") (class "Default")
      (node (ref "U$1") (pin "P17") (pinfunction "P17-RESET_P17") (pintype "bidirectional"))
    )
    (net (code "101") (name "unconnected-(U$1-P18-ADC0-PadP18)") (class "Default")
      (node (ref "U$1") (pin "P18") (pinfunction "P18-ADC0_P18") (pintype "bidirectional"))
    )
    (net (code "102") (name "unconnected-(U$1-P19-ADC1-PadP19)") (class "Default")
      (node (ref "U$1") (pin "P19") (pinfunction "P19-ADC1_P19") (pintype "bidirectional"))
    )
    (net (code "103") (name "unconnected-(U$1-P20-MISO-PadP20)") (class "Default")
      (node (ref "U$1") (pin "P20") (pinfunction "P20-MISO_P20") (pintype "bidirectional"))
    )
    (net (code "104") (name "unconnected-(U$1-P21-MOSI-PadP21)") (class "Default")
      (node (ref "U$1") (pin "P21") (pinfunction "P21-MOSI_P21") (pintype "bidirectional"))
    )
    (net (code "105") (name "unconnected-(U$1-P22-SS-PadP22)") (class "Default")
      (node (ref "U$1") (pin "P22") (pinfunction "P22-SS_P22") (pintype "bidirectional"))
    )
    (net (code "106") (name "unconnected-(U$1-P23-SCLK-PadP23)") (class "Default")
      (node (ref "U$1") (pin "P23") (pinfunction "P23-SCLK_P23") (pintype "bidirectional"))
    )
    (net (code "107") (name "unconnected-(U$1-P24-ADC2-PadP24)") (class "Default")
      (node (ref "U$1") (pin "P24") (pinfunction "P24-ADC2_P24") (pintype "bidirectional"))
    )
    (net (code "108") (name "unconnected-(U$1-P25-ADC_EXT_REF-PadP25)") (class "Default")
      (node (ref "U$1") (pin "P25") (pinfunction "P25-ADC_EXT_REF_P25") (pintype "bidirectional"))
    )
    (net (code "109") (name "unconnected-(U$1-P26-RSVD-PadP26)") (class "Default")
      (node (ref "U$1") (pin "P26") (pinfunction "P26-RSVD_P26") (pintype "bidirectional"))
    )
    (net (code "110") (name "unconnected-(U$1-P27-RSVD-PadP27)") (class "Default")
      (node (ref "U$1") (pin "P27") (pinfunction "P27-RSVD_P27") (pintype "bidirectional"))
    )
    (net (code "111") (name "unconnected-(U$1-P28-GND-PadP28)") (class "Default")
      (node (ref "U$1") (pin "P28") (pinfunction "P28-GND_P28") (pintype "bidirectional"))
    )
    (net (code "112") (name "unconnected-(U$1-P29-RSVD-PadP29)") (class "Default")
      (node (ref "U$1") (pin "P29") (pinfunction "P29-RSVD_P29") (pintype "bidirectional"))
    )
    (net (code "113") (name "unconnected-(U$2-CBS2-PadP$5)") (class "Default")
      (node (ref "U$2") (pin "P$5") (pinfunction "CBS2_P$5") (pintype "bidirectional"))
    )
    (net (code "114") (name "unconnected-(U$2-CSB-PadP$4)") (class "Default")
      (node (ref "U$2") (pin "P$4") (pinfunction "CSB_P$4") (pintype "bidirectional"))
    )
    (net (code "115") (name "unconnected-(U$2-SDO-PadP$6)") (class "Default")
      (node (ref "U$2") (pin "P$6") (pinfunction "SDO_P$6") (pintype "bidirectional"))
    )
    (net (code "116") (name "unconnected-(U$3-P2-NC-PadP2)") (class "Default")
      (node (ref "U$3") (pin "P2") (pinfunction "P2-NC_P2") (pintype "bidirectional"))
    )
    (net (code "117") (name "unconnected-(U$3-P3-NC-PadP3)") (class "Default")
      (node (ref "U$3") (pin "P3") (pinfunction "P3-NC_P3") (pintype "bidirectional"))
    )
    (net (code "118") (name "unconnected-(U$3-P4-NC-PadP4)") (class "Default")
      (node (ref "U$3") (pin "P4") (pinfunction "P4-NC_P4") (pintype "bidirectional"))
    )
    (net (code "119") (name "unconnected-(U$3-P5-NC-PadP5)") (class "Default")
      (node (ref "U$3") (pin "P5") (pinfunction "P5-NC_P5") (pintype "bidirectional"))
    )
    (net (code "120") (name "unconnected-(U$3-P6-AUX_DA-PadP6)") (class "Default")
      (node (ref "U$3") (pin "P6") (pinfunction "P6-AUX_DA_P6") (pintype "bidirectional"))
    )
    (net (code "121") (name "unconnected-(U$3-P7-AUX_CL-PadP7)") (class "Default")
      (node (ref "U$3") (pin "P7") (pinfunction "P7-AUX_CL_P7") (pintype "bidirectional"))
    )
    (net (code "122") (name "unconnected-(U$3-P12-INT-PadP12)") (class "Default")
      (node (ref "U$3") (pin "P12") (pinfunction "P12-INT_P12") (pintype "bidirectional"))
    )
    (net (code "123") (name "unconnected-(U$3-P14-NC-PadP14)") (class "Default")
      (node (ref "U$3") (pin "P14") (pinfunction "P14-NC_P14") (pintype "bidirectional"))
    )
    (net (code "124") (name "unconnected-(U$3-P15-NC-PadP15)") (class "Default")
      (node (ref "U$3") (pin "P15") (pinfunction "P15-NC_P15") (pintype "bidirectional"))
    )
    (net (code "125") (name "unconnected-(U$3-P16-NC-PadP16)") (class "Default")
      (node (ref "U$3") (pin "P16") (pinfunction "P16-NC_P16") (pintype "bidirectional"))
    )
    (net (code "126") (name "unconnected-(U$3-P17-NC-PadP17)") (class "Default")
      (node (ref "U$3") (pin "P17") (pinfunction "P17-NC_P17") (pintype "bidirectional"))
    )
    (net (code "127") (name "unconnected-(U$3-P19-RESV-PadP19)") (class "Default")
      (node (ref "U$3") (pin "P19") (pinfunction "P19-RESV_P19") (pintype "bidirectional"))
    )
    (net (code "128") (name "unconnected-(U$3-P21-RESV-PadP21)") (class "Default")
      (node (ref "U$3") (pin "P21") (pinfunction "P21-RESV_P21") (pintype "bidirectional"))
    )
    (net (code "129") (name "unconnected-(U$3-P22-CLKOUT-PadP22)") (class "Default")
      (node (ref "U$3") (pin "P22") (pinfunction "P22-CLKOUT_P22") (pintype "bidirectional"))
    )
  )
)
